# RobotWagenSchema.net
KiCad netlist of a schematic drawn in EAGLE
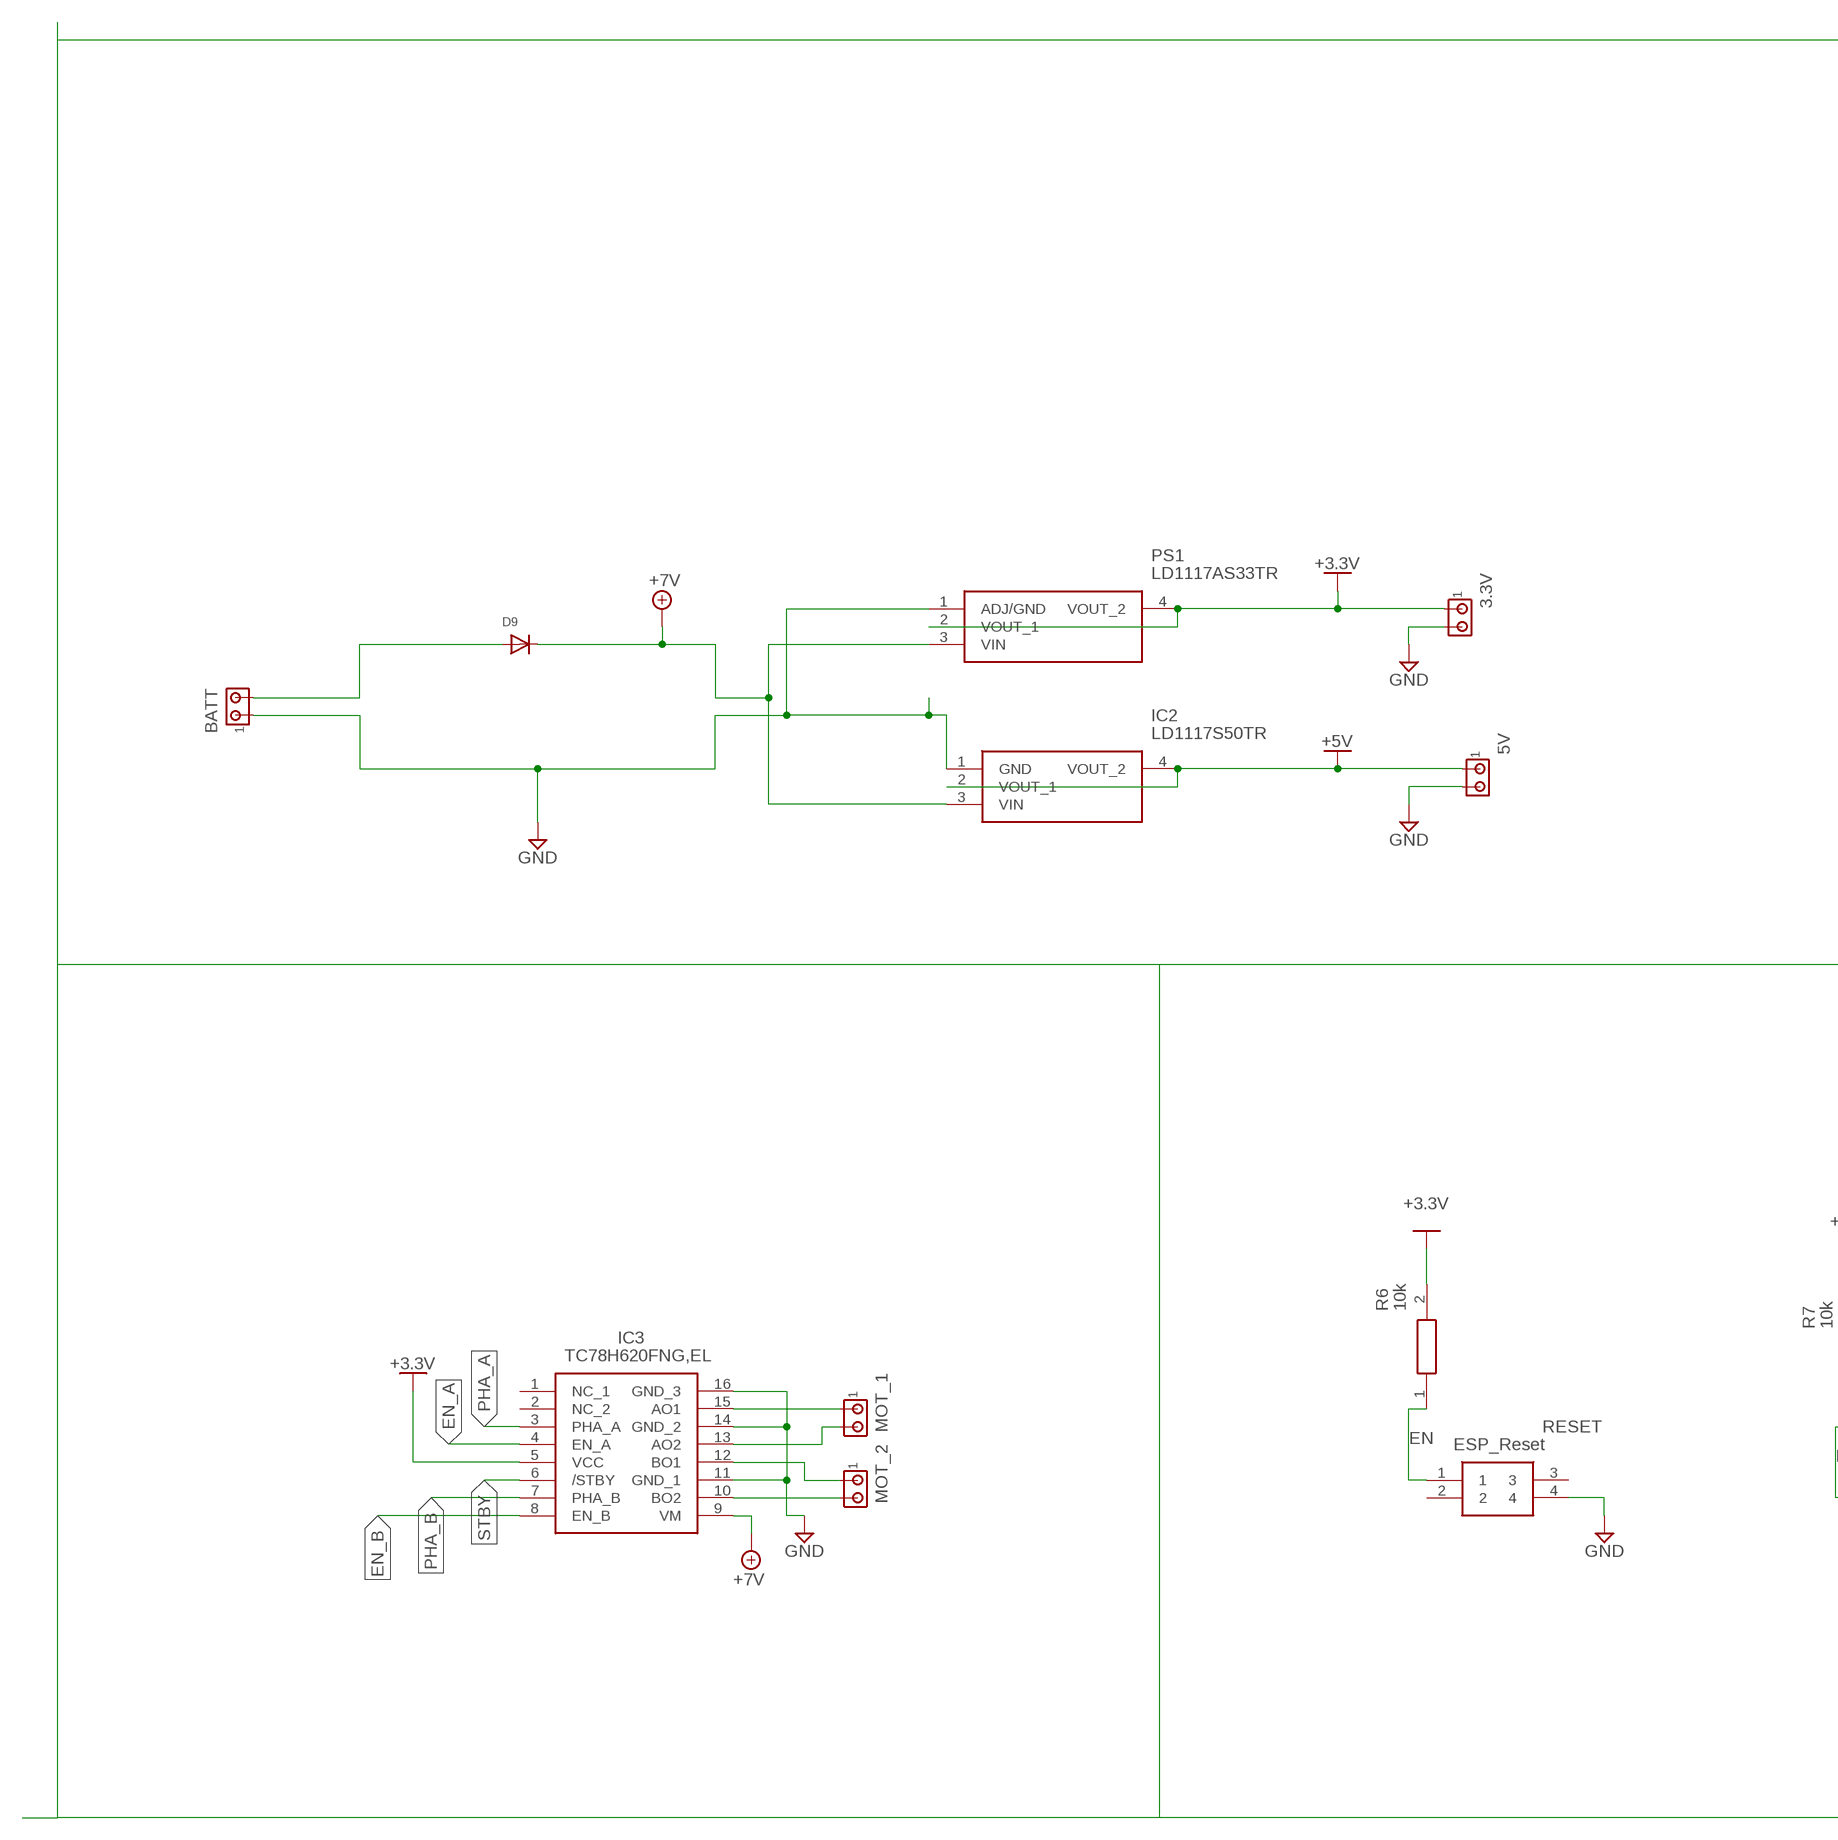
[diagram p0: schematic, sheet 1, part 1 of 2]
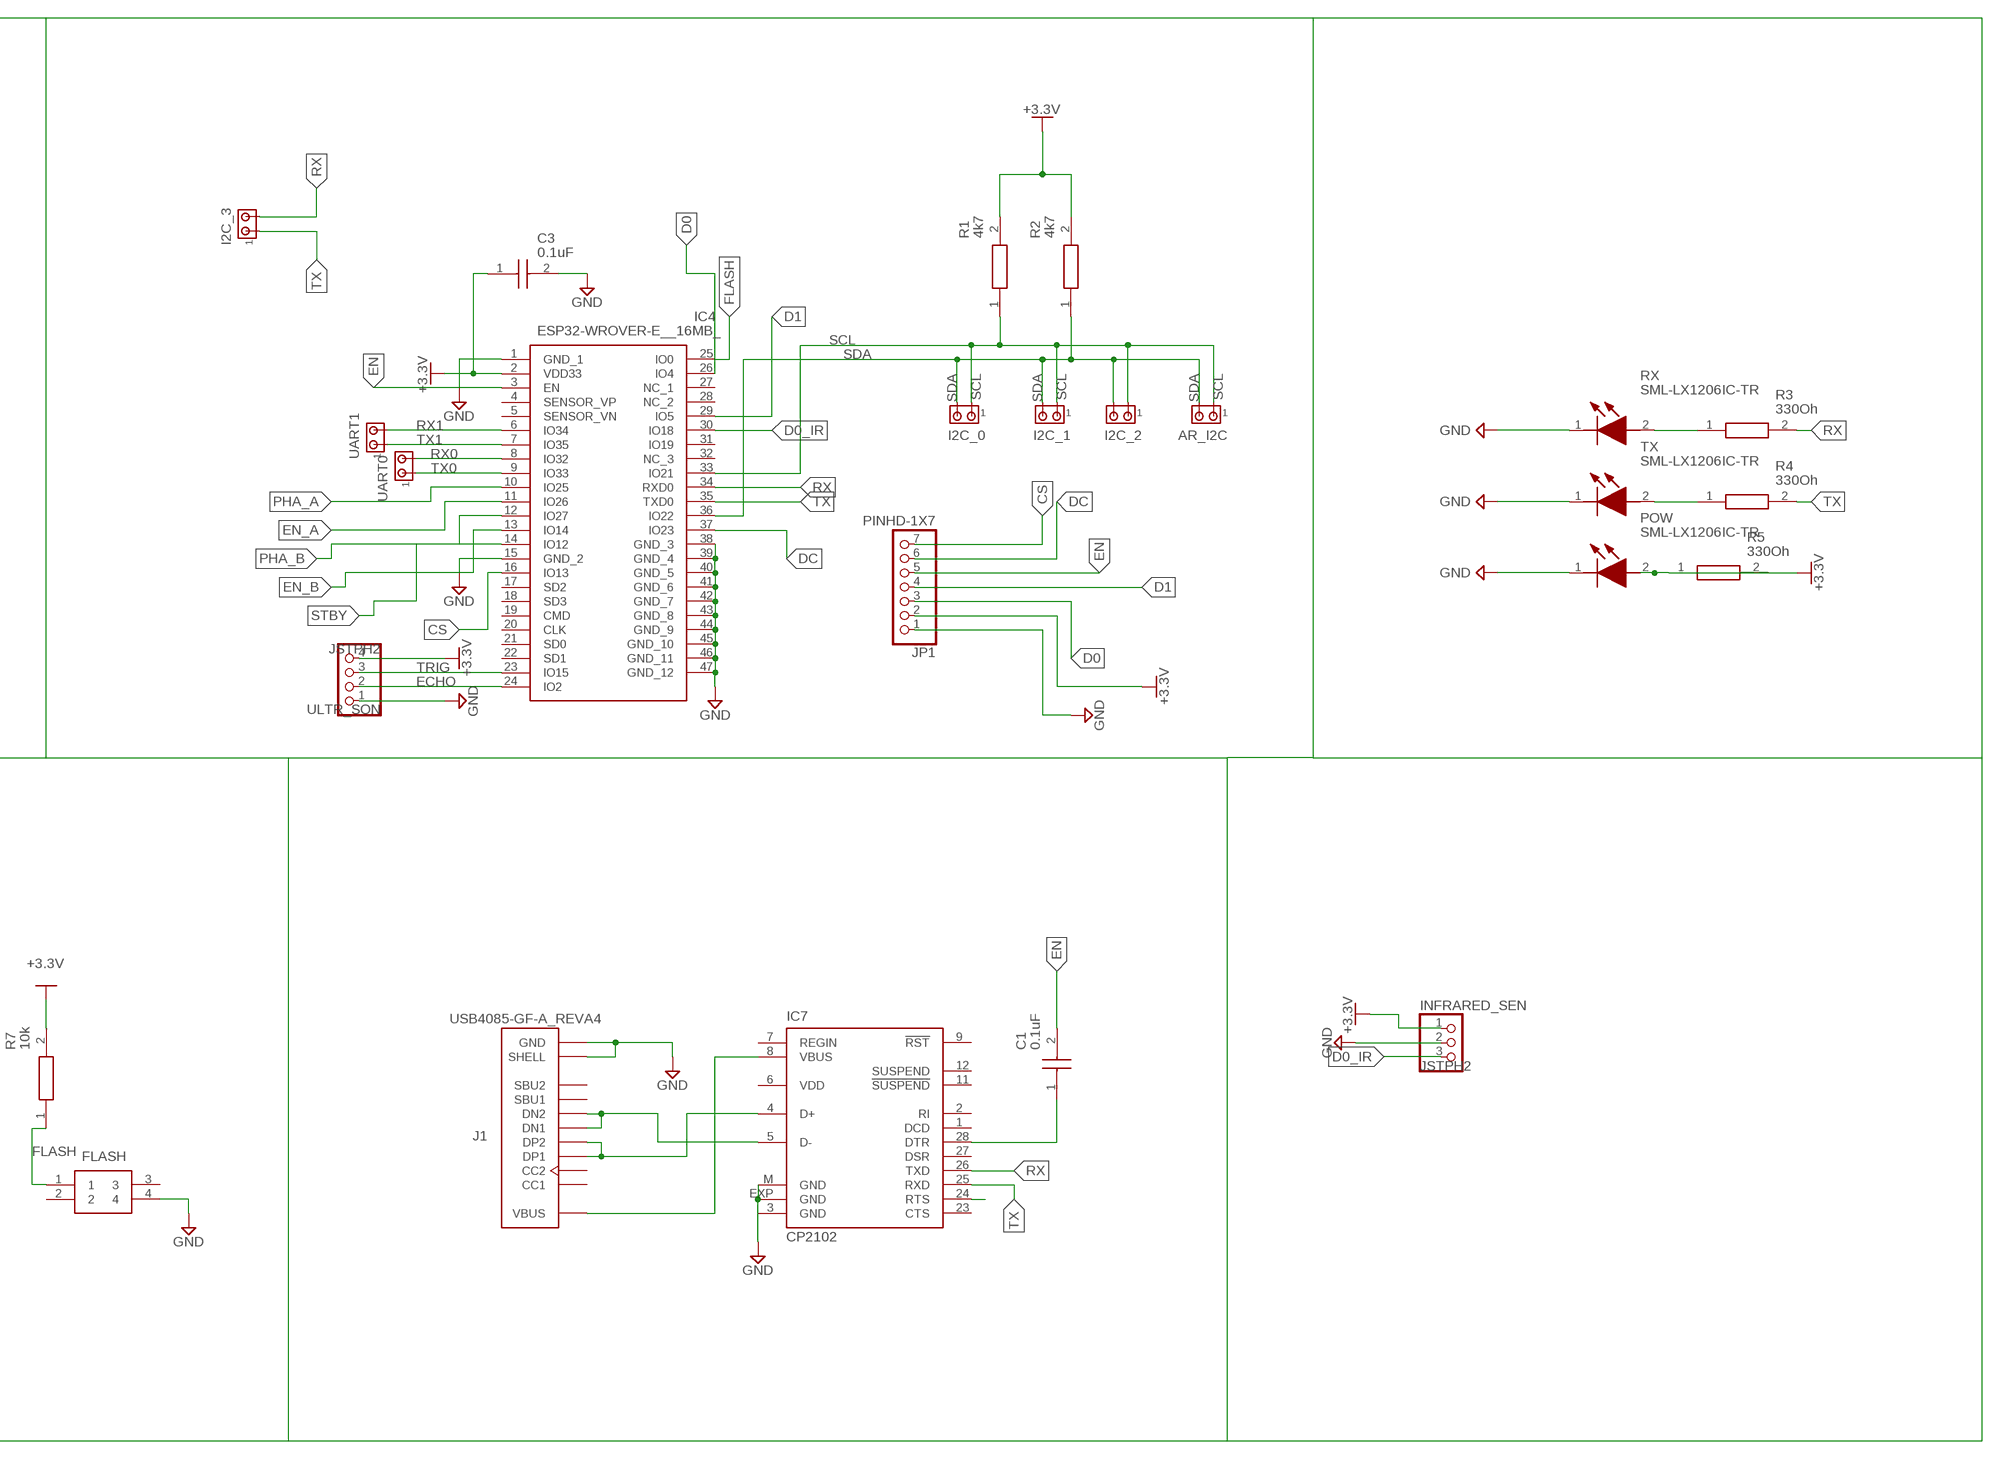
[diagram p1: schematic, sheet 1, part 2 of 2]

(export (version "E")
  (design (tool "Eeschema 10.0.6"))
  (components
    (comp (ref "3.3V")
      (value "MTA02-156")
      (footprint "eagle-import:1X2MTA")
      (libsource (lib "eagle-import") (part "MTA02-156"))
    )
    (comp (ref "5V")
      (value "MTA02-156")
      (footprint "eagle-import:1X2MTA")
      (libsource (lib "eagle-import") (part "MTA02-156"))
    )
    (comp (ref "AR_I2C")
      (value "MTA02-156")
      (footprint "eagle-import:1X2MTA")
      (libsource (lib "eagle-import") (part "MTA02-156"))
    )
    (comp (ref "BATT")
      (value "MTA02-156")
      (footprint "eagle-import:1X2MTA")
      (libsource (lib "eagle-import") (part "MTA02-156"))
    )
    (comp (ref "C1")
      (value "0.1uF")
      (footprint "eagle-import:CAPC2012X145N")
      (fields
        (field (name "ARROW_PART_NUMBER") "GRM21BR71H104JA01L")
        (field (name "MOUSER_PART_NUMBER") "81-GRM21BR71H104JA01")
      )
      (libsource (lib "eagle-import") (part "GRM21BR71H104JA01L"))
    )
    (comp (ref "C3")
      (value "0.1uF")
      (footprint "eagle-import:CAPC2012X145N")
      (fields
        (field (name "ARROW_PART_NUMBER") "GRM21BR71H104JA01L")
        (field (name "MOUSER_PART_NUMBER") "81-GRM21BR71H104JA01")
      )
      (libsource (lib "eagle-import") (part "GRM21BR71H104JA01L"))
    )
    (comp (ref "D9")
      (value "DIODESMA")
      (footprint "eagle-import:SMADIODE")
      (libsource (lib "eagle-import") (part "DIODESMA"))
    )
    (comp (ref "FLASH")
      (value "ESP_FL")
      (footprint "eagle-import:430182070816")
      (fields
        (field (name "MANUFACTURER_PART_NUMBER") "430182050816")
        (field (name "MOUSER_PART_NUMBER") "710-430182050816")
      )
      (libsource (lib "eagle-import") (part "430182050816"))
    )
    (comp (ref "I2C_0")
      (value "MTA02-156")
      (footprint "eagle-import:1X2MTA")
      (libsource (lib "eagle-import") (part "MTA02-156"))
    )
    (comp (ref "I2C_1")
      (value "MTA02-156")
      (footprint "eagle-import:1X2MTA")
      (libsource (lib "eagle-import") (part "MTA02-156"))
    )
    (comp (ref "I2C_2")
      (value "MTA02-156")
      (footprint "eagle-import:1X2MTA")
      (libsource (lib "eagle-import") (part "MTA02-156"))
    )
    (comp (ref "I2C_3")
      (value "MTA02-156")
      (footprint "eagle-import:1X2MTA")
      (libsource (lib "eagle-import") (part "MTA02-156"))
    )
    (comp (ref "IC2")
      (value "LD1117S50TR")
      (footprint "eagle-import:SOT230P700X190-4N")
      (fields (field (name "MOUSER_PART_NUMBER") "511-LD1117S50"))
      (libsource (lib "eagle-import") (part "LD1117S50TR"))
    )
    (comp (ref "IC3")
      (value "TC78H620FNG,EL")
      (footprint "eagle-import:SOP65P640X160-16N")
      (fields (field (name "MOUSER_PART_NUMBER") "757-TC78H620FNGEL"))
      (libsource (lib "eagle-import") (part "TC78H620FNG,EL"))
    )
    (comp (ref "IC4")
      (value "ESP32-WROVER-E__16MB_")
      (footprint "eagle-import:ESP32WROVERE16MB")
      (fields
        (field (name "MANUFACTURER_PART_NUMBER") "ESP32-WROVER-E (16MB)")
        (field (name "MOUSER_PART_NUMBER") "356-ESP32WRVE22864PC")
      )
      (libsource (lib "eagle-import") (part "ESP32-WROVER-E__16MB_"))
    )
    (comp (ref "IC7")
      (value "CP2102")
      (footprint "eagle-import:MLP28")
      (fields (field (name "MF") "FARNELL") (field (name "MPN") "CP2102-GM"))
      (libsource (lib "eagle-import") (part "CP2102"))
    )
    (comp (ref "INFRARED_SEN")
      (value "JSTPH2")
      (footprint "eagle-import:JSTPH2")
      (libsource (lib "eagle-import") (part "JSTPH2"))
    )
    (comp (ref "J1")
      (value "USB4085-GF-A_REVA4")
      (footprint "eagle-import:GCT_USB4085-GF-A_REVA4")
      (fields (field (name "MF") "Global Connector Technology") (field (name "MP") "USB4085-GF-A"))
      (libsource (lib "eagle-import") (part "USB4085-GF-A_REVA4"))
    )
    (comp (ref "JP1")
      (value "PINHD-1X7")
      (footprint "eagle-import:1X07")
      (libsource (lib "eagle-import") (part "PINHD-1X7"))
    )
    (comp (ref "MOT_1")
      (value "MTA02-156")
      (footprint "eagle-import:1X2MTA")
      (libsource (lib "eagle-import") (part "MTA02-156"))
    )
    (comp (ref "MOT_2")
      (value "MTA02-156")
      (footprint "eagle-import:1X2MTA")
      (libsource (lib "eagle-import") (part "MTA02-156"))
    )
    (comp (ref "POW")
      (value "SML-LX1206IC-TR")
      (footprint "eagle-import:SMLLX1206ICTR")
      (fields (field (name "MOUSER_PART_NUMBER") "696-SML-LX1206IC"))
      (libsource (lib "eagle-import") (part "SML-LX1206IC-TR"))
    )
    (comp (ref "PS1")
      (value "LD1117AS33TR")
      (footprint "eagle-import:SOT230P700X190-4N")
      (fields (field (name "MOUSER_PART_NUMBER") "511-LD1117AS33"))
      (libsource (lib "eagle-import") (part "LD1117AS33TR"))
    )
    (comp (ref "R1")
      (value "4k7")
      (footprint "eagle-import:RESC2012X65N")
      (fields (field (name "MANUFACTURER_PART_NUMBER") "WF08P473JTL"))
      (libsource (lib "eagle-import") (part "WF08P473JTL"))
    )
    (comp (ref "R2")
      (value "4k7")
      (footprint "eagle-import:RESC2012X65N")
      (fields (field (name "MANUFACTURER_PART_NUMBER") "WF08P473JTL"))
      (libsource (lib "eagle-import") (part "WF08P473JTL"))
    )
    (comp (ref "R3")
      (value "330Oh")
      (footprint "eagle-import:RESC2012X65N")
      (fields (field (name "MANUFACTURER_PART_NUMBER") "MCWR08X3301FTL"))
      (libsource (lib "eagle-import") (part "MCWR08X3301FTL"))
    )
    (comp (ref "R4")
      (value "330Oh")
      (footprint "eagle-import:RESC2012X65N")
      (fields (field (name "MANUFACTURER_PART_NUMBER") "MCWR08X3301FTL"))
      (libsource (lib "eagle-import") (part "MCWR08X3301FTL"))
    )
    (comp (ref "R5")
      (value "330Oh")
      (footprint "eagle-import:RESC2012X65N")
      (fields (field (name "MANUFACTURER_PART_NUMBER") "MCWR08X3301FTL"))
      (libsource (lib "eagle-import") (part "MCWR08X3301FTL"))
    )
    (comp (ref "R6")
      (value "10k")
      (footprint "eagle-import:RESC2012X65N")
      (fields (field (name "MANUFACTURER_PART_NUMBER") "WF08P473JTL"))
      (libsource (lib "eagle-import") (part "WF08P473JTL"))
    )
    (comp (ref "R7")
      (value "10k")
      (footprint "eagle-import:RESC2012X65N")
      (fields (field (name "MANUFACTURER_PART_NUMBER") "WF08P473JTL"))
      (libsource (lib "eagle-import") (part "WF08P473JTL"))
    )
    (comp (ref "RESET")
      (value "ESP_Reset")
      (footprint "eagle-import:430182070816")
      (fields
        (field (name "MANUFACTURER_PART_NUMBER") "430182050816")
        (field (name "MOUSER_PART_NUMBER") "710-430182050816")
      )
      (libsource (lib "eagle-import") (part "430182050816"))
    )
    (comp (ref "RX")
      (value "SML-LX1206IC-TR")
      (footprint "eagle-import:SMLLX1206ICTR")
      (fields (field (name "MOUSER_PART_NUMBER") "696-SML-LX1206IC"))
      (libsource (lib "eagle-import") (part "SML-LX1206IC-TR"))
    )
    (comp (ref "TX")
      (value "SML-LX1206IC-TR")
      (footprint "eagle-import:SMLLX1206ICTR")
      (fields (field (name "MOUSER_PART_NUMBER") "696-SML-LX1206IC"))
      (libsource (lib "eagle-import") (part "SML-LX1206IC-TR"))
    )
    (comp (ref "UART0")
      (value "MTA02-156")
      (footprint "eagle-import:1X2MTA")
      (libsource (lib "eagle-import") (part "MTA02-156"))
    )
    (comp (ref "UART1")
      (value "MTA02-156")
      (footprint "eagle-import:1X2MTA")
      (libsource (lib "eagle-import") (part "MTA02-156"))
    )
    (comp (ref "ULTR_SON")
      (value "JSTPH2")
      (footprint "eagle-import:JSTPH2")
      (libsource (lib "eagle-import") (part "jstph4_JSTPH2"))
    )
  )
  (nets
    (net (code "1") (name "+3.3V") (class "Default")
      (node (ref "3.3V") (pin "1") (pinfunction "1_1") (pintype "passive"))
      (node (ref "C3") (pin "1") (pinfunction "1_1") (pintype "bidirectional"))
      (node (ref "IC3") (pin "5") (pinfunction "VCC_5") (pintype "bidirectional"))
      (node (ref "IC4") (pin "2") (pinfunction "VDD33_2") (pintype "bidirectional"))
      (node (ref "INFRARED_SEN") (pin "1") (pinfunction "1_1") (pintype "passive"))
      (node (ref "JP1") (pin "2") (pinfunction "2_2") (pintype "passive"))
      (node (ref "POW") (pin "2") (pinfunction "A_2") (pintype "bidirectional"))
      (node (ref "PS1") (pin "2") (pinfunction "VOUT_1_2") (pintype "output"))
      (node (ref "PS1") (pin "4") (pinfunction "VOUT_2_4") (pintype "output"))
      (node (ref "R1") (pin "2") (pinfunction "2_2") (pintype "bidirectional"))
      (node (ref "R2") (pin "2") (pinfunction "2_2") (pintype "bidirectional"))
      (node (ref "R5") (pin "1") (pinfunction "1_1") (pintype "bidirectional"))
      (node (ref "R5") (pin "2") (pinfunction "2_2") (pintype "bidirectional"))
      (node (ref "R6") (pin "2") (pinfunction "2_2") (pintype "bidirectional"))
      (node (ref "R7") (pin "2") (pinfunction "2_2") (pintype "bidirectional"))
      (node (ref "ULTR_SON") (pin "4") (pinfunction "4_4") (pintype "passive"))
    )
    (net (code "2") (name "+5V") (class "Default")
      (node (ref "5V") (pin "1") (pinfunction "1_1") (pintype "passive"))
      (node (ref "IC2") (pin "2") (pinfunction "VOUT_1_2") (pintype "bidirectional"))
      (node (ref "IC2") (pin "4") (pinfunction "VOUT_2_4") (pintype "bidirectional"))
    )
    (net (code "3") (name "+7V") (class "Default")
      (node (ref "D9") (pin "C") (pinfunction "C_C") (pintype "passive"))
      (node (ref "IC2") (pin "3") (pinfunction "VIN_3") (pintype "bidirectional"))
      (node (ref "IC3") (pin "9") (pinfunction "VM_9") (pintype "bidirectional"))
      (node (ref "PS1") (pin "3") (pinfunction "VIN_3") (pintype "input"))
    )
    (net (code "4") (name "/ECHO") (class "Default")
      (node (ref "IC4") (pin "24") (pinfunction "IO2_24") (pintype "bidirectional"))
      (node (ref "ULTR_SON") (pin "2") (pinfunction "2_2") (pintype "passive"))
    )
    (net (code "5") (name "/RX0") (class "Default")
      (node (ref "IC4") (pin "8") (pinfunction "IO32_8") (pintype "bidirectional"))
      (node (ref "UART0") (pin "2") (pinfunction "2_2") (pintype "passive"))
    )
    (net (code "6") (name "/RX1") (class "Default")
      (node (ref "IC4") (pin "6") (pinfunction "IO34_6") (pintype "bidirectional"))
      (node (ref "UART1") (pin "2") (pinfunction "2_2") (pintype "passive"))
    )
    (net (code "7") (name "/SCL") (class "Default")
      (node (ref "AR_I2C") (pin "1") (pinfunction "1_1") (pintype "passive"))
      (node (ref "I2C_0") (pin "1") (pinfunction "1_1") (pintype "passive"))
      (node (ref "I2C_1") (pin "1") (pinfunction "1_1") (pintype "passive"))
      (node (ref "I2C_2") (pin "1") (pinfunction "1_1") (pintype "passive"))
      (node (ref "IC4") (pin "33") (pinfunction "IO21_33") (pintype "bidirectional"))
      (node (ref "R1") (pin "1") (pinfunction "1_1") (pintype "bidirectional"))
    )
    (net (code "8") (name "/SDA") (class "Default")
      (node (ref "AR_I2C") (pin "2") (pinfunction "2_2") (pintype "passive"))
      (node (ref "I2C_0") (pin "2") (pinfunction "2_2") (pintype "passive"))
      (node (ref "I2C_1") (pin "2") (pinfunction "2_2") (pintype "passive"))
      (node (ref "I2C_2") (pin "2") (pinfunction "2_2") (pintype "passive"))
      (node (ref "IC4") (pin "36") (pinfunction "IO22_36") (pintype "bidirectional"))
      (node (ref "R2") (pin "1") (pinfunction "1_1") (pintype "bidirectional"))
    )
    (net (code "9") (name "/TRIG") (class "Default")
      (node (ref "IC4") (pin "23") (pinfunction "IO15_23") (pintype "bidirectional"))
      (node (ref "ULTR_SON") (pin "3") (pinfunction "3_3") (pintype "passive"))
    )
    (net (code "10") (name "/TX0") (class "Default")
      (node (ref "IC4") (pin "9") (pinfunction "IO33_9") (pintype "bidirectional"))
      (node (ref "UART0") (pin "1") (pinfunction "1_1") (pintype "passive"))
    )
    (net (code "11") (name "/TX1") (class "Default")
      (node (ref "IC4") (pin "7") (pinfunction "IO35_7") (pintype "bidirectional"))
      (node (ref "UART1") (pin "1") (pinfunction "1_1") (pintype "passive"))
    )
    (net (code "12") (name "/VDD") (class "Default")
      (node (ref "IC7") (pin "6") (pinfunction "VDD_6") (pintype "power_in"))
    )
    (net (code "13") (name "CS") (class "Default")
      (node (ref "IC4") (pin "16") (pinfunction "IO13_16") (pintype "bidirectional"))
      (node (ref "JP1") (pin "7") (pinfunction "7_7") (pintype "passive"))
    )
    (net (code "14") (name "D0") (class "Default")
      (node (ref "IC4") (pin "26") (pinfunction "IO4_26") (pintype "bidirectional"))
      (node (ref "JP1") (pin "3") (pinfunction "3_3") (pintype "passive"))
    )
    (net (code "15") (name "D0_IR") (class "Default")
      (node (ref "IC4") (pin "30") (pinfunction "IO18_30") (pintype "bidirectional"))
      (node (ref "INFRARED_SEN") (pin "3") (pinfunction "3_3") (pintype "passive"))
    )
    (net (code "16") (name "D1") (class "Default")
      (node (ref "IC4") (pin "29") (pinfunction "IO5_29") (pintype "bidirectional"))
      (node (ref "JP1") (pin "4") (pinfunction "4_4") (pintype "passive"))
    )
    (net (code "17") (name "DC") (class "Default")
      (node (ref "IC4") (pin "37") (pinfunction "IO23_37") (pintype "bidirectional"))
      (node (ref "JP1") (pin "6") (pinfunction "6_6") (pintype "passive"))
    )
    (net (code "18") (name "EN") (class "Default")
      (node (ref "C1") (pin "2") (pinfunction "2_2") (pintype "bidirectional"))
      (node (ref "IC4") (pin "3") (pinfunction "EN_3") (pintype "bidirectional"))
      (node (ref "JP1") (pin "5") (pinfunction "5_5") (pintype "passive"))
      (node (ref "R6") (pin "1") (pinfunction "1_1") (pintype "bidirectional"))
      (node (ref "RESET") (pin "1") (pinfunction "1_1") (pintype "bidirectional"))
    )
    (net (code "19") (name "EN_A") (class "Default")
      (node (ref "IC3") (pin "4") (pinfunction "EN_A_4") (pintype "bidirectional"))
      (node (ref "IC4") (pin "11") (pinfunction "IO26_11") (pintype "bidirectional"))
    )
    (net (code "20") (name "EN_B") (class "Default")
      (node (ref "IC3") (pin "8") (pinfunction "EN_B_8") (pintype "bidirectional"))
      (node (ref "IC4") (pin "13") (pinfunction "IO14_13") (pintype "bidirectional"))
    )
    (net (code "21") (name "FLASH") (class "Default")
      (node (ref "FLASH") (pin "1") (pinfunction "1_1") (pintype "bidirectional"))
      (node (ref "IC4") (pin "25") (pinfunction "IO0_25") (pintype "bidirectional"))
      (node (ref "R7") (pin "1") (pinfunction "1_1") (pintype "bidirectional"))
    )
    (net (code "22") (name "GND") (class "Default")
      (node (ref "3.3V") (pin "2") (pinfunction "2_2") (pintype "passive"))
      (node (ref "5V") (pin "2") (pinfunction "2_2") (pintype "passive"))
      (node (ref "BATT") (pin "1") (pinfunction "1_1") (pintype "passive"))
      (node (ref "C3") (pin "2") (pinfunction "2_2") (pintype "bidirectional"))
      (node (ref "FLASH") (pin "4") (pinfunction "4_4") (pintype "bidirectional"))
      (node (ref "IC2") (pin "1") (pinfunction "GND_1") (pintype "bidirectional"))
      (node (ref "IC3") (pin "11") (pinfunction "GND_1_11") (pintype "bidirectional"))
      (node (ref "IC3") (pin "14") (pinfunction "GND_2_14") (pintype "bidirectional"))
      (node (ref "IC3") (pin "16") (pinfunction "GND_3_16") (pintype "bidirectional"))
      (node (ref "IC4") (pin "1") (pinfunction "GND_1_1") (pintype "bidirectional"))
      (node (ref "IC4") (pin "15") (pinfunction "GND_2_15") (pintype "bidirectional"))
      (node (ref "IC4") (pin "38") (pinfunction "GND_3_38") (pintype "bidirectional"))
      (node (ref "IC4") (pin "39") (pinfunction "GND_4_39") (pintype "bidirectional"))
      (node (ref "IC4") (pin "40") (pinfunction "GND_5_40") (pintype "bidirectional"))
      (node (ref "IC4") (pin "41") (pinfunction "GND_6_41") (pintype "bidirectional"))
      (node (ref "IC4") (pin "42") (pinfunction "GND_7_42") (pintype "bidirectional"))
      (node (ref "IC4") (pin "43") (pinfunction "GND_8_43") (pintype "bidirectional"))
      (node (ref "IC4") (pin "44") (pinfunction "GND_9_44") (pintype "bidirectional"))
      (node (ref "IC4") (pin "45") (pinfunction "GND_10_45") (pintype "bidirectional"))
      (node (ref "IC4") (pin "46") (pinfunction "GND_11_46") (pintype "bidirectional"))
      (node (ref "IC4") (pin "47") (pinfunction "GND_12_47") (pintype "bidirectional"))
      (node (ref "IC7") (pin "3") (pinfunction "GND_3") (pintype "power_in"))
      (node (ref "IC7") (pin "EXP") (pinfunction "GND_EXP") (pintype "power_in"))
      (node (ref "IC7") (pin "M") (pinfunction "GND_M") (pintype "power_in"))
      (node (ref "INFRARED_SEN") (pin "2") (pinfunction "2_2") (pintype "passive"))
      (node (ref "J1") (pin "A1") (pinfunction "GND_A1") (pintype "passive"))
      (node (ref "J1") (pin "A12") (pinfunction "GND_A12") (pintype "passive"))
      (node (ref "J1") (pin "B1") (pinfunction "GND_B1") (pintype "passive"))
      (node (ref "J1") (pin "B12") (pinfunction "GND_B12") (pintype "passive"))
      (node (ref "J1") (pin "P1") (pinfunction "SHELL_P1") (pintype "passive"))
      (node (ref "J1") (pin "P2") (pinfunction "SHELL_P2") (pintype "passive"))
      (node (ref "J1") (pin "P3") (pinfunction "SHELL_P3") (pintype "passive"))
      (node (ref "J1") (pin "P4") (pinfunction "SHELL_P4") (pintype "passive"))
      (node (ref "JP1") (pin "1") (pinfunction "1_1") (pintype "passive"))
      (node (ref "POW") (pin "1") (pinfunction "K_1") (pintype "bidirectional"))
      (node (ref "PS1") (pin "1") (pinfunction "ADJ/GND_1") (pintype "power_in"))
      (node (ref "RESET") (pin "4") (pinfunction "4_4") (pintype "bidirectional"))
      (node (ref "RX") (pin "1") (pinfunction "K_1") (pintype "bidirectional"))
      (node (ref "TX") (pin "1") (pinfunction "K_1") (pintype "bidirectional"))
      (node (ref "ULTR_SON") (pin "1") (pinfunction "1_1") (pintype "passive"))
    )
    (net (code "23") (name "Net-(BATT-Pad2)") (class "Default")
      (node (ref "BATT") (pin "2") (pinfunction "2_2") (pintype "passive"))
      (node (ref "D9") (pin "A") (pinfunction "A_A") (pintype "passive"))
    )
    (net (code "24") (name "Net-(IC3-AO1)") (class "Default")
      (node (ref "IC3") (pin "15") (pinfunction "AO1_15") (pintype "bidirectional"))
      (node (ref "MOT_1") (pin "1") (pinfunction "1_1") (pintype "passive"))
    )
    (net (code "25") (name "Net-(IC3-AO2)") (class "Default")
      (node (ref "IC3") (pin "13") (pinfunction "AO2_13") (pintype "bidirectional"))
      (node (ref "MOT_1") (pin "2") (pinfunction "2_2") (pintype "passive"))
    )
    (net (code "26") (name "Net-(IC3-BO1)") (class "Default")
      (node (ref "IC3") (pin "12") (pinfunction "BO1_12") (pintype "bidirectional"))
      (node (ref "MOT_2") (pin "1") (pinfunction "1_1") (pintype "passive"))
    )
    (net (code "27") (name "Net-(IC3-BO2)") (class "Default")
      (node (ref "IC3") (pin "10") (pinfunction "BO2_10") (pintype "bidirectional"))
      (node (ref "MOT_2") (pin "2") (pinfunction "2_2") (pintype "passive"))
    )
    (net (code "28") (name "Net-(IC7-D+)") (class "Default")
      (node (ref "IC7") (pin "4") (pinfunction "D+_4") (pintype "bidirectional"))
      (node (ref "J1") (pin "A6") (pinfunction "DP1_A6") (pintype "bidirectional"))
      (node (ref "J1") (pin "B6") (pinfunction "DP2_B6") (pintype "bidirectional"))
    )
    (net (code "29") (name "Net-(IC7-D-)") (class "Default")
      (node (ref "IC7") (pin "5") (pinfunction "D-_5") (pintype "bidirectional"))
      (node (ref "J1") (pin "A7") (pinfunction "DN1_A7") (pintype "bidirectional"))
      (node (ref "J1") (pin "B7") (pinfunction "DN2_B7") (pintype "bidirectional"))
    )
    (net (code "30") (name "Net-(IC7-DTR)") (class "Default")
      (node (ref "C1") (pin "1") (pinfunction "1_1") (pintype "bidirectional"))
      (node (ref "IC7") (pin "28") (pinfunction "DTR_28") (pintype "output"))
    )
    (net (code "31") (name "Net-(IC7-VBUS)") (class "Default")
      (node (ref "IC7") (pin "8") (pinfunction "VBUS_8") (pintype "input"))
      (node (ref "J1") (pin "A4") (pinfunction "VBUS_A4") (pintype "power_in"))
      (node (ref "J1") (pin "A9") (pinfunction "VBUS_A9") (pintype "power_in"))
      (node (ref "J1") (pin "B4") (pinfunction "VBUS_B4") (pintype "power_in"))
      (node (ref "J1") (pin "B9") (pinfunction "VBUS_B9") (pintype "power_in"))
    )
    (net (code "32") (name "Net-(RX-A)") (class "Default")
      (node (ref "R3") (pin "1") (pinfunction "1_1") (pintype "bidirectional"))
      (node (ref "RX") (pin "2") (pinfunction "A_2") (pintype "bidirectional"))
    )
    (net (code "33") (name "PHA_A") (class "Default")
      (node (ref "IC3") (pin "3") (pinfunction "PHA_A_3") (pintype "bidirectional"))
      (node (ref "IC4") (pin "10") (pinfunction "IO25_10") (pintype "bidirectional"))
    )
    (net (code "34") (name "PHA_B") (class "Default")
      (node (ref "IC3") (pin "7") (pinfunction "PHA_B_7") (pintype "bidirectional"))
      (node (ref "IC4") (pin "12") (pinfunction "IO27_12") (pintype "bidirectional"))
    )
    (net (code "35") (name "RX") (class "Default")
      (node (ref "I2C_3") (pin "2") (pinfunction "2_2") (pintype "passive"))
      (node (ref "IC4") (pin "34") (pinfunction "RXD0_34") (pintype "bidirectional"))
      (node (ref "IC7") (pin "26") (pinfunction "TXD_26") (pintype "output"))
      (node (ref "R3") (pin "2") (pinfunction "2_2") (pintype "bidirectional"))
    )
    (net (code "36") (name "STBY") (class "Default")
      (node (ref "IC3") (pin "6") (pinfunction "/STBY_6") (pintype "bidirectional"))
      (node (ref "IC4") (pin "14") (pinfunction "IO12_14") (pintype "bidirectional"))
    )
    (net (code "37") (name "TX") (class "Default")
      (node (ref "I2C_3") (pin "1") (pinfunction "1_1") (pintype "passive"))
      (node (ref "IC4") (pin "35") (pinfunction "TXD0_35") (pintype "bidirectional"))
      (node (ref "IC7") (pin "25") (pinfunction "RXD_25") (pintype "input"))
      (node (ref "R4") (pin "1") (pinfunction "1_1") (pintype "bidirectional"))
      (node (ref "R4") (pin "2") (pinfunction "2_2") (pintype "bidirectional"))
      (node (ref "TX") (pin "2") (pinfunction "A_2") (pintype "bidirectional"))
    )
    (net (code "38") (name "unconnected-(FLASH-Pad2)") (class "Default")
      (node (ref "FLASH") (pin "2") (pinfunction "2_2") (pintype "bidirectional"))
    )
    (net (code "39") (name "unconnected-(FLASH-Pad3)") (class "Default")
      (node (ref "FLASH") (pin "3") (pinfunction "3_3") (pintype "bidirectional"))
    )
    (net (code "40") (name "unconnected-(IC3-NC_1-Pad1)") (class "Default")
      (node (ref "IC3") (pin "1") (pinfunction "NC_1_1") (pintype "bidirectional"))
    )
    (net (code "41") (name "unconnected-(IC3-NC_2-Pad2)") (class "Default")
      (node (ref "IC3") (pin "2") (pinfunction "NC_2_2") (pintype "bidirectional"))
    )
    (net (code "42") (name "unconnected-(IC4-CLK-Pad20)") (class "Default")
      (node (ref "IC4") (pin "20") (pinfunction "CLK_20") (pintype "bidirectional"))
    )
    (net (code "43") (name "unconnected-(IC4-CMD-Pad19)") (class "Default")
      (node (ref "IC4") (pin "19") (pinfunction "CMD_19") (pintype "bidirectional"))
    )
    (net (code "44") (name "unconnected-(IC4-IO19-Pad31)") (class "Default")
      (node (ref "IC4") (pin "31") (pinfunction "IO19_31") (pintype "bidirectional"))
    )
    (net (code "45") (name "unconnected-(IC4-NC_1-Pad27)") (class "Default")
      (node (ref "IC4") (pin "27") (pinfunction "NC_1_27") (pintype "bidirectional"))
    )
    (net (code "46") (name "unconnected-(IC4-NC_2-Pad28)") (class "Default")
      (node (ref "IC4") (pin "28") (pinfunction "NC_2_28") (pintype "bidirectional"))
    )
    (net (code "47") (name "unconnected-(IC4-NC_3-Pad32)") (class "Default")
      (node (ref "IC4") (pin "32") (pinfunction "NC_3_32") (pintype "bidirectional"))
    )
    (net (code "48") (name "unconnected-(IC4-SD0-Pad21)") (class "Default")
      (node (ref "IC4") (pin "21") (pinfunction "SD0_21") (pintype "bidirectional"))
    )
    (net (code "49") (name "unconnected-(IC4-SD1-Pad22)") (class "Default")
      (node (ref "IC4") (pin "22") (pinfunction "SD1_22") (pintype "bidirectional"))
    )
    (net (code "50") (name "unconnected-(IC4-SD2-Pad17)") (class "Default")
      (node (ref "IC4") (pin "17") (pinfunction "SD2_17") (pintype "bidirectional"))
    )
    (net (code "51") (name "unconnected-(IC4-SD3-Pad18)") (class "Default")
      (node (ref "IC4") (pin "18") (pinfunction "SD3_18") (pintype "bidirectional"))
    )
    (net (code "52") (name "unconnected-(IC4-SENSOR_VN-Pad5)") (class "Default")
      (node (ref "IC4") (pin "5") (pinfunction "SENSOR_VN_5") (pintype "bidirectional"))
    )
    (net (code "53") (name "unconnected-(IC4-SENSOR_VP-Pad4)") (class "Default")
      (node (ref "IC4") (pin "4") (pinfunction "SENSOR_VP_4") (pintype "bidirectional"))
    )
    (net (code "54") (name "unconnected-(IC7-CTS-Pad23)") (class "Default")
      (node (ref "IC7") (pin "23") (pinfunction "CTS_23") (pintype "input"))
    )
    (net (code "55") (name "unconnected-(IC7-DCD-Pad1)") (class "Default")
      (node (ref "IC7") (pin "1") (pinfunction "DCD_1") (pintype "input"))
    )
    (net (code "56") (name "unconnected-(IC7-DSR-Pad27)") (class "Default")
      (node (ref "IC7") (pin "27") (pinfunction "DSR_27") (pintype "input"))
    )
    (net (code "57") (name "unconnected-(IC7-REGIN-Pad7)") (class "Default")
      (node (ref "IC7") (pin "7") (pinfunction "REGIN_7") (pintype "passive"))
    )
    (net (code "58") (name "unconnected-(IC7-RI-Pad2)") (class "Default")
      (node (ref "IC7") (pin "2") (pinfunction "RI_2") (pintype "input"))
    )
    (net (code "59") (name "unconnected-(IC7-RTS-Pad24)") (class "Default")
      (node (ref "IC7") (pin "24") (pinfunction "RTS_24") (pintype "output"))
    )
    (net (code "60") (name "unconnected-(IC7-SUSPEND-Pad12)") (class "Default")
      (node (ref "IC7") (pin "12") (pinfunction "SUSPEND_12") (pintype "output"))
    )
    (net (code "61") (name "unconnected-(IC7-~{RST}-Pad9)") (class "Default")
      (node (ref "IC7") (pin "9") (pinfunction "~{RST}_9") (pintype "bidirectional"))
    )
    (net (code "62") (name "unconnected-(IC7-~{SUSPEND}-Pad11)") (class "Default")
      (node (ref "IC7") (pin "11") (pinfunction "~{SUSPEND}_11") (pintype "output"))
    )
    (net (code "63") (name "unconnected-(J1-CC1-PadA5)") (class "Default")
      (node (ref "J1") (pin "A5") (pinfunction "CC1_A5") (pintype "bidirectional"))
    )
    (net (code "64") (name "unconnected-(J1-CC2-PadB5)") (class "Default")
      (node (ref "J1") (pin "B5") (pinfunction "CC2_B5") (pintype "bidirectional"))
    )
    (net (code "65") (name "unconnected-(J1-SBU1-PadA8)") (class "Default")
      (node (ref "J1") (pin "A8") (pinfunction "SBU1_A8") (pintype "bidirectional"))
    )
    (net (code "66") (name "unconnected-(J1-SBU2-PadB8)") (class "Default")
      (node (ref "J1") (pin "B8") (pinfunction "SBU2_B8") (pintype "bidirectional"))
    )
    (net (code "67") (name "unconnected-(RESET-Pad2)") (class "Default")
      (node (ref "RESET") (pin "2") (pinfunction "2_2") (pintype "bidirectional"))
    )
    (net (code "68") (name "unconnected-(RESET-Pad3)") (class "Default")
      (node (ref "RESET") (pin "3") (pinfunction "3_3") (pintype "bidirectional"))
    )
  )
)
